# 38kHzSensorRevB2.net
KiCad netlist of a schematic drawn in EAGLE
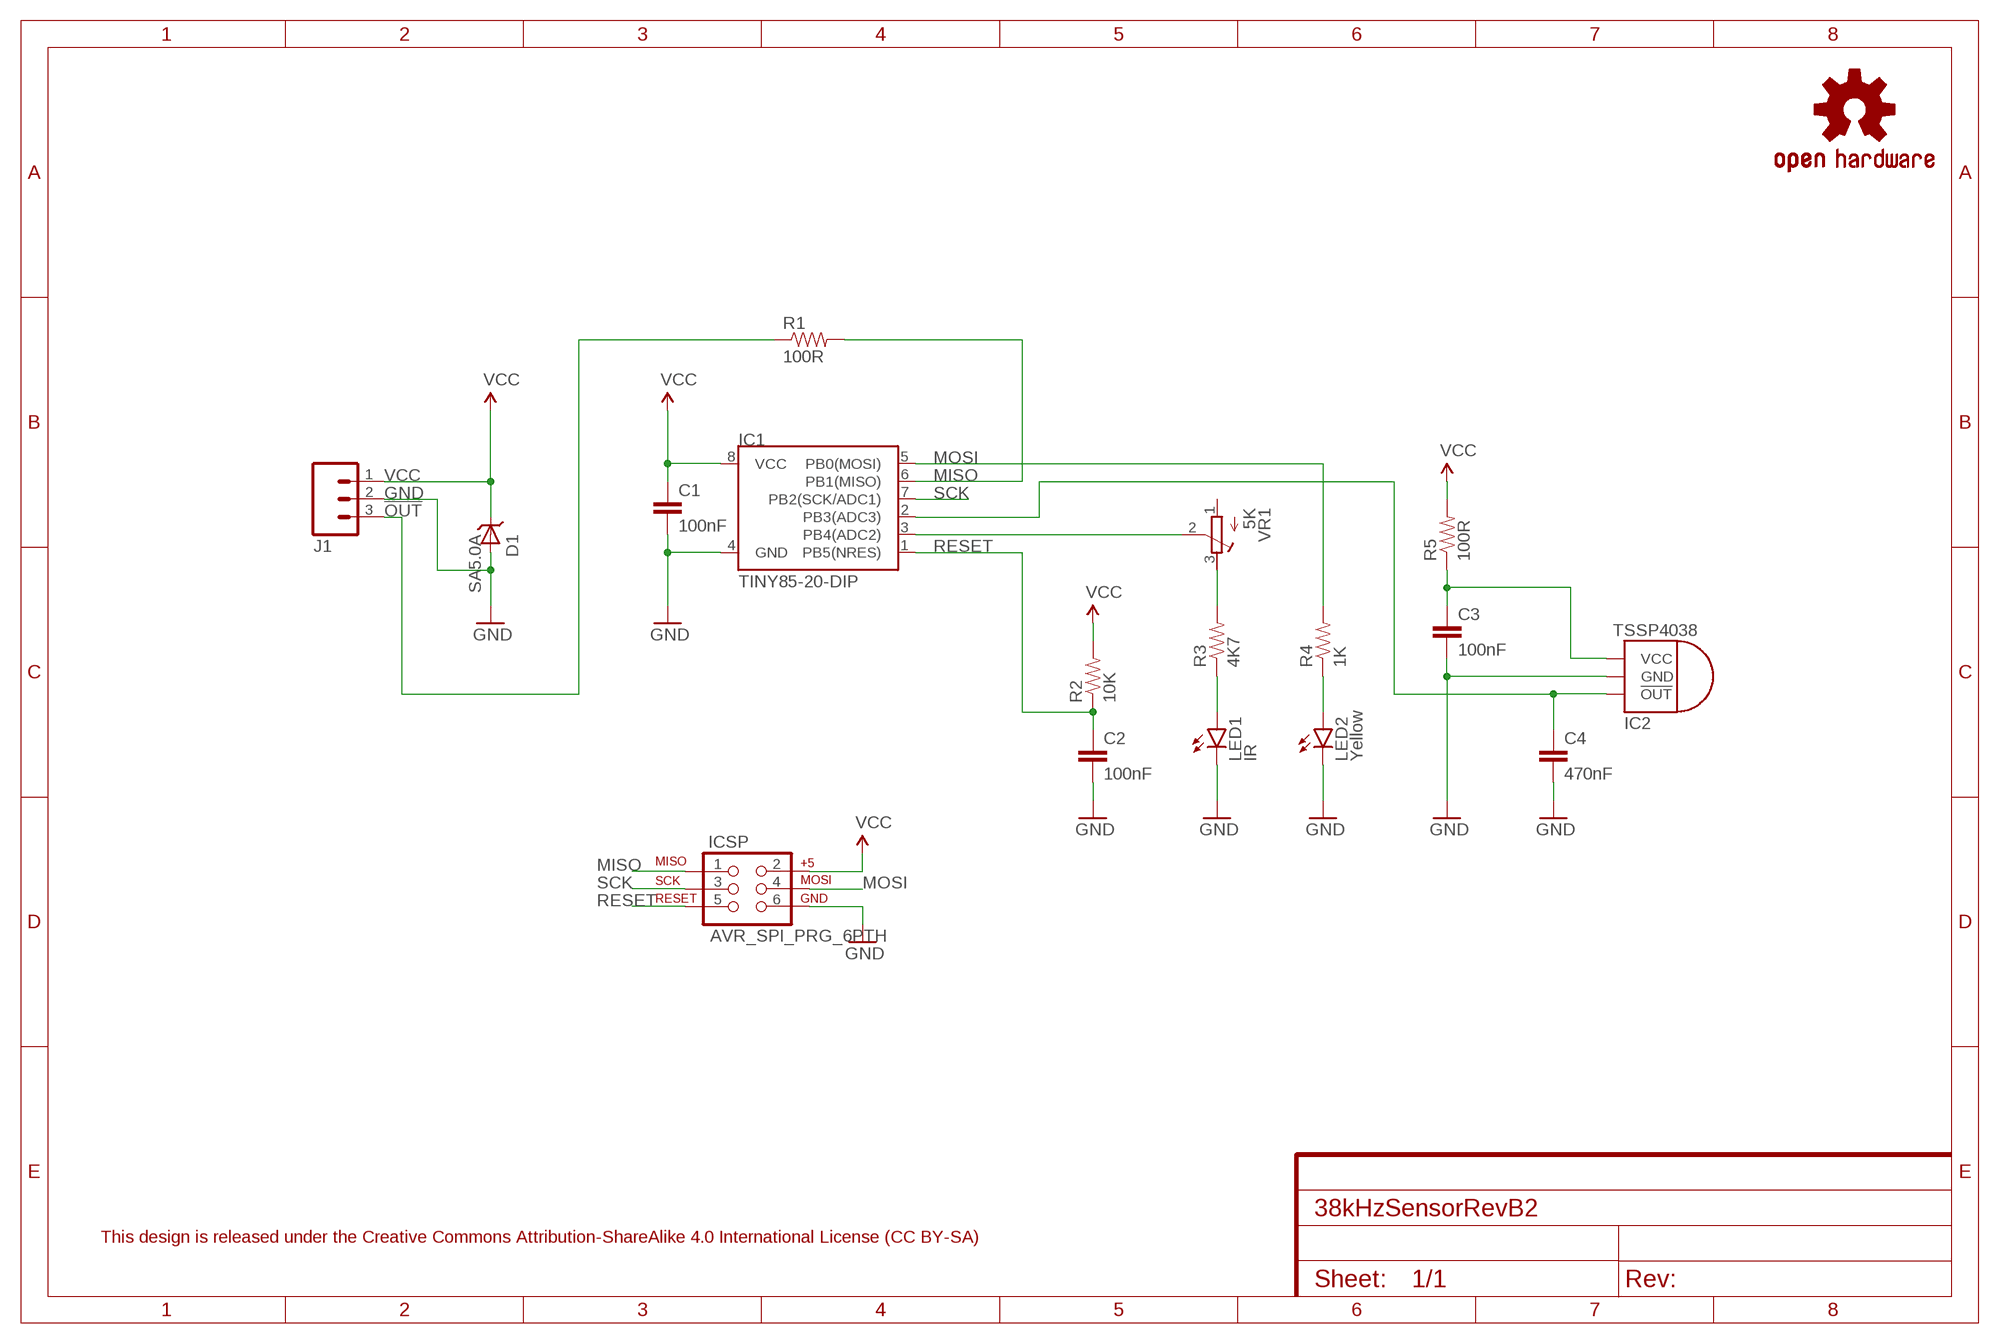
[diagram p0: schematic, sheet 1]

(export (version "E")
  (design (tool "Eeschema 10.0.6"))
  (components
    (comp (ref "C1")
      (value "100nF")
      (footprint "eagle-import:CAP-PTH-SMALL")
      (libsource (lib "eagle-import") (part "CAPPTH"))
    )
    (comp (ref "C2")
      (value "100nF")
      (footprint "eagle-import:CAP-PTH-SMALL")
      (libsource (lib "eagle-import") (part "CAPPTH"))
    )
    (comp (ref "C3")
      (value "100nF")
      (footprint "eagle-import:CAP-PTH-SMALL")
      (libsource (lib "eagle-import") (part "CAPPTH"))
    )
    (comp (ref "C4")
      (value "470nF")
      (footprint "eagle-import:CAP-PTH-5MM")
      (libsource (lib "eagle-import") (part "CAPPTH1"))
    )
    (comp (ref "D1")
      (value "SA5.0A")
      (footprint "eagle-import:DO41_TVS_UNI")
      (libsource (lib "eagle-import") (part "SA5.0A"))
    )
    (comp (ref "IC1")
      (value "TINY85-20-DIP")
      (footprint "eagle-import:DIP08")
      (libsource (lib "eagle-import") (part "ATTINY45TINY85-20-DIP"))
    )
    (comp (ref "IC2")
      (value "TSSP4038EDGE")
      (footprint "eagle-import:TSSP4038_PKG_EDGE")
      (libsource (lib "eagle-import") (part "TSSP4038EDGE"))
    )
    (comp (ref "ICSP")
      (value "AVR_SPI_PRG_6PTH")
      (footprint "eagle-import:2X3")
      (libsource (lib "eagle-import") (part "AVR_SPI_PRG_6PTH"))
    )
    (comp (ref "J1")
      (value "M03PTH")
      (footprint "eagle-import:1X03")
      (libsource (lib "eagle-import") (part "M03PTH"))
    )
    (comp (ref "LED1")
      (value "IR")
      (footprint "eagle-import:LED5MM")
      (libsource (lib "eagle-import") (part "LED5MM"))
    )
    (comp (ref "LED2")
      (value "Yellow")
      (footprint "eagle-import:LED3MM")
      (libsource (lib "eagle-import") (part "LED3MM"))
    )
    (comp (ref "LOGO1")
      (value "OSHW-LOGOS")
      (footprint "eagle-import:OSHW-LOGO-S")
      (libsource (lib "eagle-import") (part "OSHW-LOGOS"))
    )
    (comp (ref "R1")
      (value "100R")
      (footprint "eagle-import:AXIAL-0.4")
      (libsource (lib "eagle-import") (part "RESISTORPTH-1/4W"))
    )
    (comp (ref "R2")
      (value "10K")
      (footprint "eagle-import:AXIAL-0.4")
      (libsource (lib "eagle-import") (part "RESISTORPTH-1/4W"))
    )
    (comp (ref "R3")
      (value "4K7")
      (footprint "eagle-import:AXIAL-0.4")
      (libsource (lib "eagle-import") (part "RESISTORPTH-1/4W"))
    )
    (comp (ref "R4")
      (value "1K")
      (footprint "eagle-import:AXIAL-0.4")
      (libsource (lib "eagle-import") (part "RESISTORPTH-1/4W"))
    )
    (comp (ref "R5")
      (value "100R")
      (footprint "eagle-import:AXIAL-0.4")
      (libsource (lib "eagle-import") (part "RESISTORPTH-1/4W"))
    )
    (comp (ref "VR1")
      (value "5K")
      (footprint "eagle-import:RTRIM3296X")
      (libsource (lib "eagle-import") (part "R-TRIMM3296X"))
    )
  )
  (nets
    (net (code "1") (name "/MISO") (class "Default")
      (node (ref "IC1") (pin "6") (pinfunction "PB1(MISO)_6") (pintype "bidirectional"))
      (node (ref "ICSP") (pin "1") (pinfunction "1_1") (pintype "passive"))
      (node (ref "R1") (pin "P$2") (pinfunction "2_P$2") (pintype "passive"))
    )
    (net (code "2") (name "/MOSI") (class "Default")
      (node (ref "IC1") (pin "5") (pinfunction "PB0(MOSI)_5") (pintype "bidirectional"))
      (node (ref "ICSP") (pin "4") (pinfunction "4_4") (pintype "passive"))
      (node (ref "R4") (pin "P$2") (pinfunction "2_P$2") (pintype "passive"))
    )
    (net (code "3") (name "/RESET") (class "Default")
      (node (ref "C2") (pin "1") (pinfunction "1_1") (pintype "passive"))
      (node (ref "IC1") (pin "1") (pinfunction "PB5(NRES)_1") (pintype "bidirectional"))
      (node (ref "ICSP") (pin "5") (pinfunction "5_5") (pintype "passive"))
      (node (ref "R2") (pin "P$1") (pinfunction "1_P$1") (pintype "passive"))
    )
    (net (code "4") (name "/SCK") (class "Default")
      (node (ref "IC1") (pin "7") (pinfunction "PB2(SCK/ADC1)_7") (pintype "bidirectional"))
      (node (ref "ICSP") (pin "3") (pinfunction "3_3") (pintype "passive"))
    )
    (net (code "5") (name "/~{OUT}") (class "Default")
      (node (ref "J1") (pin "3") (pinfunction "3_3") (pintype "passive"))
      (node (ref "R1") (pin "P$1") (pinfunction "1_P$1") (pintype "passive"))
    )
    (net (code "6") (name "GND") (class "Default")
      (node (ref "C1") (pin "2") (pinfunction "2_2") (pintype "passive"))
      (node (ref "C2") (pin "2") (pinfunction "2_2") (pintype "passive"))
      (node (ref "C3") (pin "2") (pinfunction "2_2") (pintype "passive"))
      (node (ref "C4") (pin "2") (pinfunction "2_2") (pintype "passive"))
      (node (ref "D1") (pin "ANODE") (pinfunction "ANODE_ANODE") (pintype "passive"))
      (node (ref "IC1") (pin "4") (pinfunction "GND_4") (pintype "bidirectional"))
      (node (ref "IC2") (pin "GND") (pinfunction "GND_GND") (pintype "bidirectional"))
      (node (ref "ICSP") (pin "6") (pinfunction "6_6") (pintype "passive"))
      (node (ref "J1") (pin "2") (pinfunction "2_2") (pintype "passive"))
      (node (ref "LED1") (pin "K") (pinfunction "C_K") (pintype "passive"))
      (node (ref "LED2") (pin "K") (pinfunction "C_K") (pintype "passive"))
    )
    (net (code "7") (name "Net-(IC1-PB3(ADC3))") (class "Default")
      (node (ref "C4") (pin "1") (pinfunction "1_1") (pintype "passive"))
      (node (ref "IC1") (pin "2") (pinfunction "PB3(ADC3)_2") (pintype "bidirectional"))
      (node (ref "IC2") (pin "OUT") (pinfunction "~{OUT}_OUT") (pintype "bidirectional"))
    )
    (net (code "8") (name "Net-(IC1-PB4(ADC2))") (class "Default")
      (node (ref "IC1") (pin "3") (pinfunction "PB4(ADC2)_3") (pintype "bidirectional"))
      (node (ref "VR1") (pin "2") (pinfunction "S_2") (pintype "passive"))
    )
    (net (code "9") (name "Net-(R3-1)") (class "Default")
      (node (ref "LED1") (pin "A") (pinfunction "A_A") (pintype "passive"))
      (node (ref "R3") (pin "P$1") (pinfunction "1_P$1") (pintype "passive"))
    )
    (net (code "10") (name "Net-(R3-2)") (class "Default")
      (node (ref "R3") (pin "P$2") (pinfunction "2_P$2") (pintype "passive"))
      (node (ref "VR1") (pin "3") (pinfunction "E_3") (pintype "passive"))
    )
    (net (code "11") (name "Net-(R4-1)") (class "Default")
      (node (ref "LED2") (pin "A") (pinfunction "A_A") (pintype "passive"))
      (node (ref "R4") (pin "P$1") (pinfunction "1_P$1") (pintype "passive"))
    )
    (net (code "12") (name "Net-(R5-1)") (class "Default")
      (node (ref "C3") (pin "1") (pinfunction "1_1") (pintype "passive"))
      (node (ref "IC2") (pin "VCC") (pinfunction "VCC_VCC") (pintype "bidirectional"))
      (node (ref "R5") (pin "P$1") (pinfunction "1_P$1") (pintype "passive"))
    )
    (net (code "13") (name "VCC") (class "Default")
      (node (ref "C1") (pin "1") (pinfunction "1_1") (pintype "passive"))
      (node (ref "D1") (pin "CATHODE") (pinfunction "CATHODE_CATHODE") (pintype "passive"))
      (node (ref "IC1") (pin "8") (pinfunction "VCC_8") (pintype "bidirectional"))
      (node (ref "ICSP") (pin "2") (pinfunction "2_2") (pintype "passive"))
      (node (ref "J1") (pin "1") (pinfunction "1_1") (pintype "passive"))
      (node (ref "R2") (pin "P$2") (pinfunction "2_P$2") (pintype "passive"))
      (node (ref "R5") (pin "P$2") (pinfunction "2_P$2") (pintype "passive"))
    )
    (net (code "14") (name "unconnected-(VR1-A-Pad1)") (class "Default")
      (node (ref "VR1") (pin "1") (pinfunction "A_1") (pintype "passive"))
    )
  )
)
